# sensor_unitv3.net
KiCad netlist of a schematic drawn in EAGLE
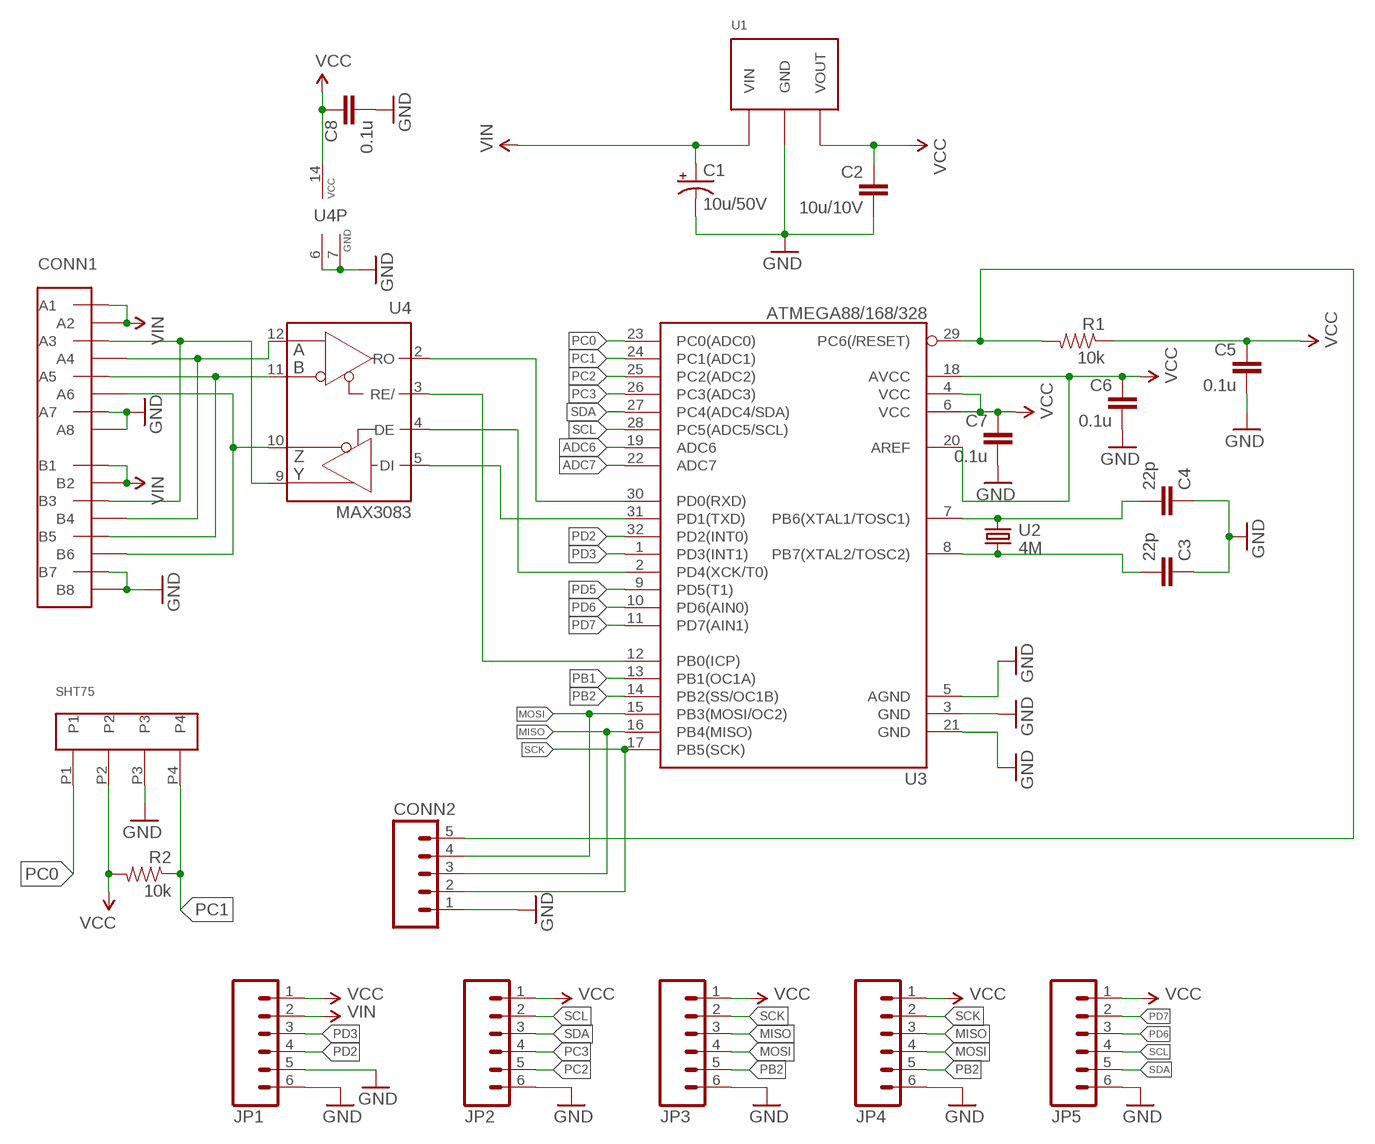
[diagram p0: schematic, sheet 1]

(export (version "E")
  (design (tool "Eeschema 10.0.6"))
  (components
    (comp (ref "C1")
      (value "10u/50V")
      (footprint "eagle-import:PANASONIC_C")
      (libsource (lib "eagle-import") (part "CAP_POLC"))
    )
    (comp (ref "C2")
      (value "10u/10V")
      (footprint "eagle-import:0805")
      (libsource (lib "eagle-import") (part "CAP0805"))
    )
    (comp (ref "C3")
      (value "22p")
      (footprint "eagle-import:0805")
      (libsource (lib "eagle-import") (part "CAP0805"))
    )
    (comp (ref "C4")
      (value "22p")
      (footprint "eagle-import:0805")
      (libsource (lib "eagle-import") (part "CAP0805"))
    )
    (comp (ref "C5")
      (value "0.1u")
      (footprint "eagle-import:0805")
      (libsource (lib "eagle-import") (part "CAP0805"))
    )
    (comp (ref "C6")
      (value "0.1u")
      (footprint "eagle-import:0805")
      (libsource (lib "eagle-import") (part "CAP0805"))
    )
    (comp (ref "C7")
      (value "0.1u")
      (footprint "eagle-import:0805")
      (libsource (lib "eagle-import") (part "CAP0805"))
    )
    (comp (ref "C8")
      (value "0.1u")
      (footprint "eagle-import:0805")
      (libsource (lib "eagle-import") (part "CAP0805"))
    )
    (comp (ref "CONN1")
      (value "4UCON-04950")
      (footprint "eagle-import:4UCON-04950")
      (libsource (lib "eagle-import") (part "4UCON-04950"))
    )
    (comp (ref "CONN2")
      (value "M05LOCK")
      (footprint "eagle-import:1X05_LOCK")
      (libsource (lib "eagle-import") (part "M05LOCK"))
    )
    (comp (ref "JP1")
      (value "M06LOCK_LONGPADS")
      (footprint "eagle-import:1X06_LOCK_LONGPADS")
      (libsource (lib "eagle-import") (part "M06LOCK_LONGPADS"))
    )
    (comp (ref "JP2")
      (value "M06LOCK_LONGPADS")
      (footprint "eagle-import:1X06_LOCK_LONGPADS")
      (libsource (lib "eagle-import") (part "M06LOCK_LONGPADS"))
    )
    (comp (ref "JP3")
      (value "M06LOCK_LONGPADS")
      (footprint "eagle-import:1X06_LOCK_LONGPADS")
      (libsource (lib "eagle-import") (part "M06LOCK_LONGPADS"))
    )
    (comp (ref "JP4")
      (value "M06LOCK_LONGPADS")
      (footprint "eagle-import:1X06_LOCK_LONGPADS")
      (libsource (lib "eagle-import") (part "M06LOCK_LONGPADS"))
    )
    (comp (ref "JP5")
      (value "M06LOCK_LONGPADS")
      (footprint "eagle-import:1X06_LOCK_LONGPADS")
      (libsource (lib "eagle-import") (part "M06LOCK_LONGPADS"))
    )
    (comp (ref "R1")
      (value "10k")
      (footprint "eagle-import:0805")
      (libsource (lib "eagle-import") (part "RESISTOR0805-RES"))
    )
    (comp (ref "R2")
      (value "10k")
      (footprint "eagle-import:0805")
      (libsource (lib "eagle-import") (part "RESISTOR0805-RES"))
    )
    (comp (ref "SHT75")
      (value "MM852-43-004-20")
      (footprint "eagle-import:MM851-43-004-20")
      (libsource (lib "eagle-import") (part "MM852-43-004-20"))
    )
    (comp (ref "U1")
      (value "OKI-78SR")
      (footprint "eagle-import:OKI-78SR")
      (libsource (lib "eagle-import") (part "OKI-78SR"))
    )
    (comp (ref "U2")
      (value "4M")
      (footprint "eagle-import:HC49UP")
      (libsource (lib "eagle-import") (part "CRYSTALHC49UP"))
    )
    (comp (ref "U3")
      (value "ATMEGA88/168/328")
      (footprint "eagle-import:TQFP32-08")
      (libsource (lib "eagle-import") (part "ATMEGA168"))
    )
    (comp (ref "U4")
      (value "MAX3083")
      (footprint "eagle-import:SO14")
      (fields (field (name "MF") "MAXIM") (field (name "MPN") "MAX489CSD"))
      (libsource (lib "eagle-import") (part "MAX489CSD"))
    )
  )
  (nets
    (net (code "1") (name "ADC6") (class "Default")
      (node (ref "U3") (pin "19") (pinfunction "ADC6_19") (pintype "bidirectional"))
    )
    (net (code "2") (name "ADC7") (class "Default")
      (node (ref "U3") (pin "22") (pinfunction "ADC7_22") (pintype "bidirectional"))
    )
    (net (code "3") (name "GND") (class "Default")
      (node (ref "C1") (pin "-") (pinfunction "-_-") (pintype "passive"))
      (node (ref "C2") (pin "2") (pinfunction "2_2") (pintype "passive"))
      (node (ref "C3") (pin "1") (pinfunction "1_1") (pintype "passive"))
      (node (ref "C4") (pin "1") (pinfunction "1_1") (pintype "passive"))
      (node (ref "C5") (pin "2") (pinfunction "2_2") (pintype "passive"))
      (node (ref "C6") (pin "2") (pinfunction "2_2") (pintype "passive"))
      (node (ref "C7") (pin "2") (pinfunction "2_2") (pintype "passive"))
      (node (ref "C8") (pin "2") (pinfunction "2_2") (pintype "passive"))
      (node (ref "CONN1") (pin "A7") (pinfunction "A7_A7") (pintype "bidirectional"))
      (node (ref "CONN1") (pin "A8") (pinfunction "A8_A8") (pintype "bidirectional"))
      (node (ref "CONN1") (pin "B7") (pinfunction "B7_B7") (pintype "bidirectional"))
      (node (ref "CONN1") (pin "B8") (pinfunction "B8_B8") (pintype "bidirectional"))
      (node (ref "CONN2") (pin "1") (pinfunction "1_1") (pintype "passive"))
      (node (ref "JP1") (pin "5") (pinfunction "5_5") (pintype "passive"))
      (node (ref "JP1") (pin "6") (pinfunction "6_6") (pintype "passive"))
      (node (ref "JP2") (pin "6") (pinfunction "6_6") (pintype "passive"))
      (node (ref "JP3") (pin "6") (pinfunction "6_6") (pintype "passive"))
      (node (ref "JP4") (pin "6") (pinfunction "6_6") (pintype "passive"))
      (node (ref "JP5") (pin "6") (pinfunction "6_6") (pintype "passive"))
      (node (ref "SHT75") (pin "P3") (pinfunction "P3_P3") (pintype "bidirectional"))
      (node (ref "U1") (pin "GND") (pinfunction "GND_GND") (pintype "bidirectional"))
      (node (ref "U3") (pin "21") (pinfunction "GND_21") (pintype "bidirectional"))
      (node (ref "U3") (pin "3") (pinfunction "GND_3") (pintype "bidirectional"))
      (node (ref "U3") (pin "5") (pinfunction "AGND_5") (pintype "bidirectional"))
      (node (ref "U4") (pin "6") (pinfunction "GND_6") (pintype "power_in"))
      (node (ref "U4") (pin "7") (pinfunction "GND_7") (pintype "power_in"))
    )
    (net (code "4") (name "MISO") (class "Default")
      (node (ref "CONN2") (pin "3") (pinfunction "3_3") (pintype "passive"))
      (node (ref "JP3") (pin "3") (pinfunction "3_3") (pintype "passive"))
      (node (ref "JP4") (pin "3") (pinfunction "3_3") (pintype "passive"))
      (node (ref "U3") (pin "16") (pinfunction "PB4(MISO)_16") (pintype "bidirectional"))
    )
    (net (code "5") (name "MOSI") (class "Default")
      (node (ref "CONN2") (pin "4") (pinfunction "4_4") (pintype "passive"))
      (node (ref "JP3") (pin "4") (pinfunction "4_4") (pintype "passive"))
      (node (ref "JP4") (pin "4") (pinfunction "4_4") (pintype "passive"))
      (node (ref "U3") (pin "15") (pinfunction "PB3(MOSI/OC2)_15") (pintype "bidirectional"))
    )
    (net (code "6") (name "Net-(U3-PB0(ICP))") (class "Default")
      (node (ref "U3") (pin "12") (pinfunction "PB0(ICP)_12") (pintype "bidirectional"))
      (node (ref "U4") (pin "3") (pinfunction "RE/_3") (pintype "input"))
    )
    (net (code "7") (name "Net-(U3-PB6(XTAL1{slash}TOSC1))") (class "Default")
      (node (ref "C4") (pin "2") (pinfunction "2_2") (pintype "passive"))
      (node (ref "U2") (pin "2") (pinfunction "2_2") (pintype "passive"))
      (node (ref "U3") (pin "7") (pinfunction "PB6(XTAL1/TOSC1)_7") (pintype "bidirectional"))
    )
    (net (code "8") (name "Net-(U3-PB7(XTAL2{slash}TOSC2))") (class "Default")
      (node (ref "C3") (pin "2") (pinfunction "2_2") (pintype "passive"))
      (node (ref "U2") (pin "1") (pinfunction "1_1") (pintype "passive"))
      (node (ref "U3") (pin "8") (pinfunction "PB7(XTAL2/TOSC2)_8") (pintype "bidirectional"))
    )
    (net (code "9") (name "Net-(U3-PC6({slash}RESET))") (class "Default")
      (node (ref "CONN2") (pin "5") (pinfunction "5_5") (pintype "passive"))
      (node (ref "R1") (pin "2") (pinfunction "2_2") (pintype "passive"))
      (node (ref "U3") (pin "29") (pinfunction "PC6(/RESET)_29") (pintype "bidirectional"))
    )
    (net (code "10") (name "Net-(U3-PD0(RXD))") (class "Default")
      (node (ref "U3") (pin "30") (pinfunction "PD0(RXD)_30") (pintype "bidirectional"))
      (node (ref "U4") (pin "2") (pinfunction "RO_2") (pintype "output"))
    )
    (net (code "11") (name "Net-(U3-PD1(TXD))") (class "Default")
      (node (ref "U3") (pin "31") (pinfunction "PD1(TXD)_31") (pintype "bidirectional"))
      (node (ref "U4") (pin "5") (pinfunction "DI_5") (pintype "input"))
    )
    (net (code "12") (name "Net-(U3-PD4(XCK{slash}T0))") (class "Default")
      (node (ref "U3") (pin "2") (pinfunction "PD4(XCK/T0)_2") (pintype "bidirectional"))
      (node (ref "U4") (pin "4") (pinfunction "DE_4") (pintype "input"))
    )
    (net (code "13") (name "Net-(U4D-A)") (class "Default")
      (node (ref "CONN1") (pin "A4") (pinfunction "A4_A4") (pintype "bidirectional"))
      (node (ref "CONN1") (pin "B4") (pinfunction "B4_B4") (pintype "bidirectional"))
      (node (ref "U4") (pin "12") (pinfunction "A_12") (pintype "passive"))
    )
    (net (code "14") (name "Net-(U4D-B)") (class "Default")
      (node (ref "CONN1") (pin "A5") (pinfunction "A5_A5") (pintype "bidirectional"))
      (node (ref "CONN1") (pin "B5") (pinfunction "B5_B5") (pintype "bidirectional"))
      (node (ref "U4") (pin "11") (pinfunction "B_11") (pintype "passive"))
    )
    (net (code "15") (name "Net-(U4D-Y)") (class "Default")
      (node (ref "CONN1") (pin "A3") (pinfunction "A3_A3") (pintype "bidirectional"))
      (node (ref "CONN1") (pin "B3") (pinfunction "B3_B3") (pintype "bidirectional"))
      (node (ref "U4") (pin "9") (pinfunction "Y_9") (pintype "passive"))
    )
    (net (code "16") (name "Net-(U4D-Z)") (class "Default")
      (node (ref "CONN1") (pin "A6") (pinfunction "A6_A6") (pintype "bidirectional"))
      (node (ref "CONN1") (pin "B6") (pinfunction "B6_B6") (pintype "bidirectional"))
      (node (ref "U4") (pin "10") (pinfunction "Z_10") (pintype "passive"))
    )
    (net (code "17") (name "PB1") (class "Default")
      (node (ref "U3") (pin "13") (pinfunction "PB1(OC1A)_13") (pintype "bidirectional"))
    )
    (net (code "18") (name "PB2") (class "Default")
      (node (ref "JP3") (pin "5") (pinfunction "5_5") (pintype "passive"))
      (node (ref "JP4") (pin "5") (pinfunction "5_5") (pintype "passive"))
      (node (ref "U3") (pin "14") (pinfunction "PB2(SS/OC1B)_14") (pintype "bidirectional"))
    )
    (net (code "19") (name "PC0") (class "Default")
      (node (ref "SHT75") (pin "P1") (pinfunction "P1_P1") (pintype "bidirectional"))
      (node (ref "U3") (pin "23") (pinfunction "PC0(ADC0)_23") (pintype "bidirectional"))
    )
    (net (code "20") (name "PC1") (class "Default")
      (node (ref "R2") (pin "1") (pinfunction "1_1") (pintype "passive"))
      (node (ref "SHT75") (pin "P4") (pinfunction "P4_P4") (pintype "bidirectional"))
      (node (ref "U3") (pin "24") (pinfunction "PC1(ADC1)_24") (pintype "bidirectional"))
    )
    (net (code "21") (name "PC2") (class "Default")
      (node (ref "JP2") (pin "5") (pinfunction "5_5") (pintype "passive"))
      (node (ref "U3") (pin "25") (pinfunction "PC2(ADC2)_25") (pintype "bidirectional"))
    )
    (net (code "22") (name "PC3") (class "Default")
      (node (ref "JP2") (pin "4") (pinfunction "4_4") (pintype "passive"))
      (node (ref "U3") (pin "26") (pinfunction "PC3(ADC3)_26") (pintype "bidirectional"))
    )
    (net (code "23") (name "PD2") (class "Default")
      (node (ref "JP1") (pin "4") (pinfunction "4_4") (pintype "passive"))
      (node (ref "U3") (pin "32") (pinfunction "PD2(INT0)_32") (pintype "bidirectional"))
    )
    (net (code "24") (name "PD3") (class "Default")
      (node (ref "JP1") (pin "3") (pinfunction "3_3") (pintype "passive"))
      (node (ref "U3") (pin "1") (pinfunction "PD3(INT1)_1") (pintype "bidirectional"))
    )
    (net (code "25") (name "PD5") (class "Default")
      (node (ref "U3") (pin "9") (pinfunction "PD5(T1)_9") (pintype "bidirectional"))
    )
    (net (code "26") (name "PD6") (class "Default")
      (node (ref "JP5") (pin "3") (pinfunction "3_3") (pintype "passive"))
      (node (ref "U3") (pin "10") (pinfunction "PD6(AIN0)_10") (pintype "bidirectional"))
    )
    (net (code "27") (name "PD7") (class "Default")
      (node (ref "JP5") (pin "2") (pinfunction "2_2") (pintype "passive"))
      (node (ref "U3") (pin "11") (pinfunction "PD7(AIN1)_11") (pintype "bidirectional"))
    )
    (net (code "28") (name "SCK") (class "Default")
      (node (ref "CONN2") (pin "2") (pinfunction "2_2") (pintype "passive"))
      (node (ref "JP3") (pin "2") (pinfunction "2_2") (pintype "passive"))
      (node (ref "JP4") (pin "2") (pinfunction "2_2") (pintype "passive"))
      (node (ref "U3") (pin "17") (pinfunction "PB5(SCK)_17") (pintype "bidirectional"))
    )
    (net (code "29") (name "SCL") (class "Default")
      (node (ref "JP2") (pin "2") (pinfunction "2_2") (pintype "passive"))
      (node (ref "JP5") (pin "4") (pinfunction "4_4") (pintype "passive"))
      (node (ref "U3") (pin "28") (pinfunction "PC5(ADC5/SCL)_28") (pintype "bidirectional"))
    )
    (net (code "30") (name "SDA") (class "Default")
      (node (ref "JP2") (pin "3") (pinfunction "3_3") (pintype "passive"))
      (node (ref "JP5") (pin "5") (pinfunction "5_5") (pintype "passive"))
      (node (ref "U3") (pin "27") (pinfunction "PC4(ADC4/SDA)_27") (pintype "bidirectional"))
    )
    (net (code "31") (name "VCC") (class "Default")
      (node (ref "C2") (pin "1") (pinfunction "1_1") (pintype "passive"))
      (node (ref "C5") (pin "1") (pinfunction "1_1") (pintype "passive"))
      (node (ref "C6") (pin "1") (pinfunction "1_1") (pintype "passive"))
      (node (ref "C7") (pin "1") (pinfunction "1_1") (pintype "passive"))
      (node (ref "C8") (pin "1") (pinfunction "1_1") (pintype "passive"))
      (node (ref "JP1") (pin "1") (pinfunction "1_1") (pintype "passive"))
      (node (ref "JP2") (pin "1") (pinfunction "1_1") (pintype "passive"))
      (node (ref "JP3") (pin "1") (pinfunction "1_1") (pintype "passive"))
      (node (ref "JP4") (pin "1") (pinfunction "1_1") (pintype "passive"))
      (node (ref "JP5") (pin "1") (pinfunction "1_1") (pintype "passive"))
      (node (ref "R1") (pin "1") (pinfunction "1_1") (pintype "passive"))
      (node (ref "R2") (pin "2") (pinfunction "2_2") (pintype "passive"))
      (node (ref "SHT75") (pin "P2") (pinfunction "P2_P2") (pintype "bidirectional"))
      (node (ref "U1") (pin "VOUT") (pinfunction "VOUT_VOUT") (pintype "bidirectional"))
      (node (ref "U3") (pin "18") (pinfunction "AVCC_18") (pintype "bidirectional"))
      (node (ref "U3") (pin "20") (pinfunction "AREF_20") (pintype "bidirectional"))
      (node (ref "U3") (pin "4") (pinfunction "VCC_4") (pintype "bidirectional"))
      (node (ref "U3") (pin "6") (pinfunction "VCC_6") (pintype "bidirectional"))
      (node (ref "U4") (pin "14") (pinfunction "VCC_14") (pintype "power_in"))
    )
    (net (code "32") (name "VIN") (class "Default")
      (node (ref "C1") (pin "+") (pinfunction "+_+") (pintype "passive"))
      (node (ref "CONN1") (pin "A1") (pinfunction "A1_A1") (pintype "bidirectional"))
      (node (ref "CONN1") (pin "A2") (pinfunction "A2_A2") (pintype "bidirectional"))
      (node (ref "CONN1") (pin "B1") (pinfunction "B1_B1") (pintype "bidirectional"))
      (node (ref "CONN1") (pin "B2") (pinfunction "B2_B2") (pintype "bidirectional"))
      (node (ref "JP1") (pin "2") (pinfunction "2_2") (pintype "passive"))
      (node (ref "U1") (pin "VIN") (pinfunction "VIN_VIN") (pintype "bidirectional"))
    )
  )
)
